# SenseBox-Shield_v10.net
KiCad netlist of a schematic drawn in EAGLE
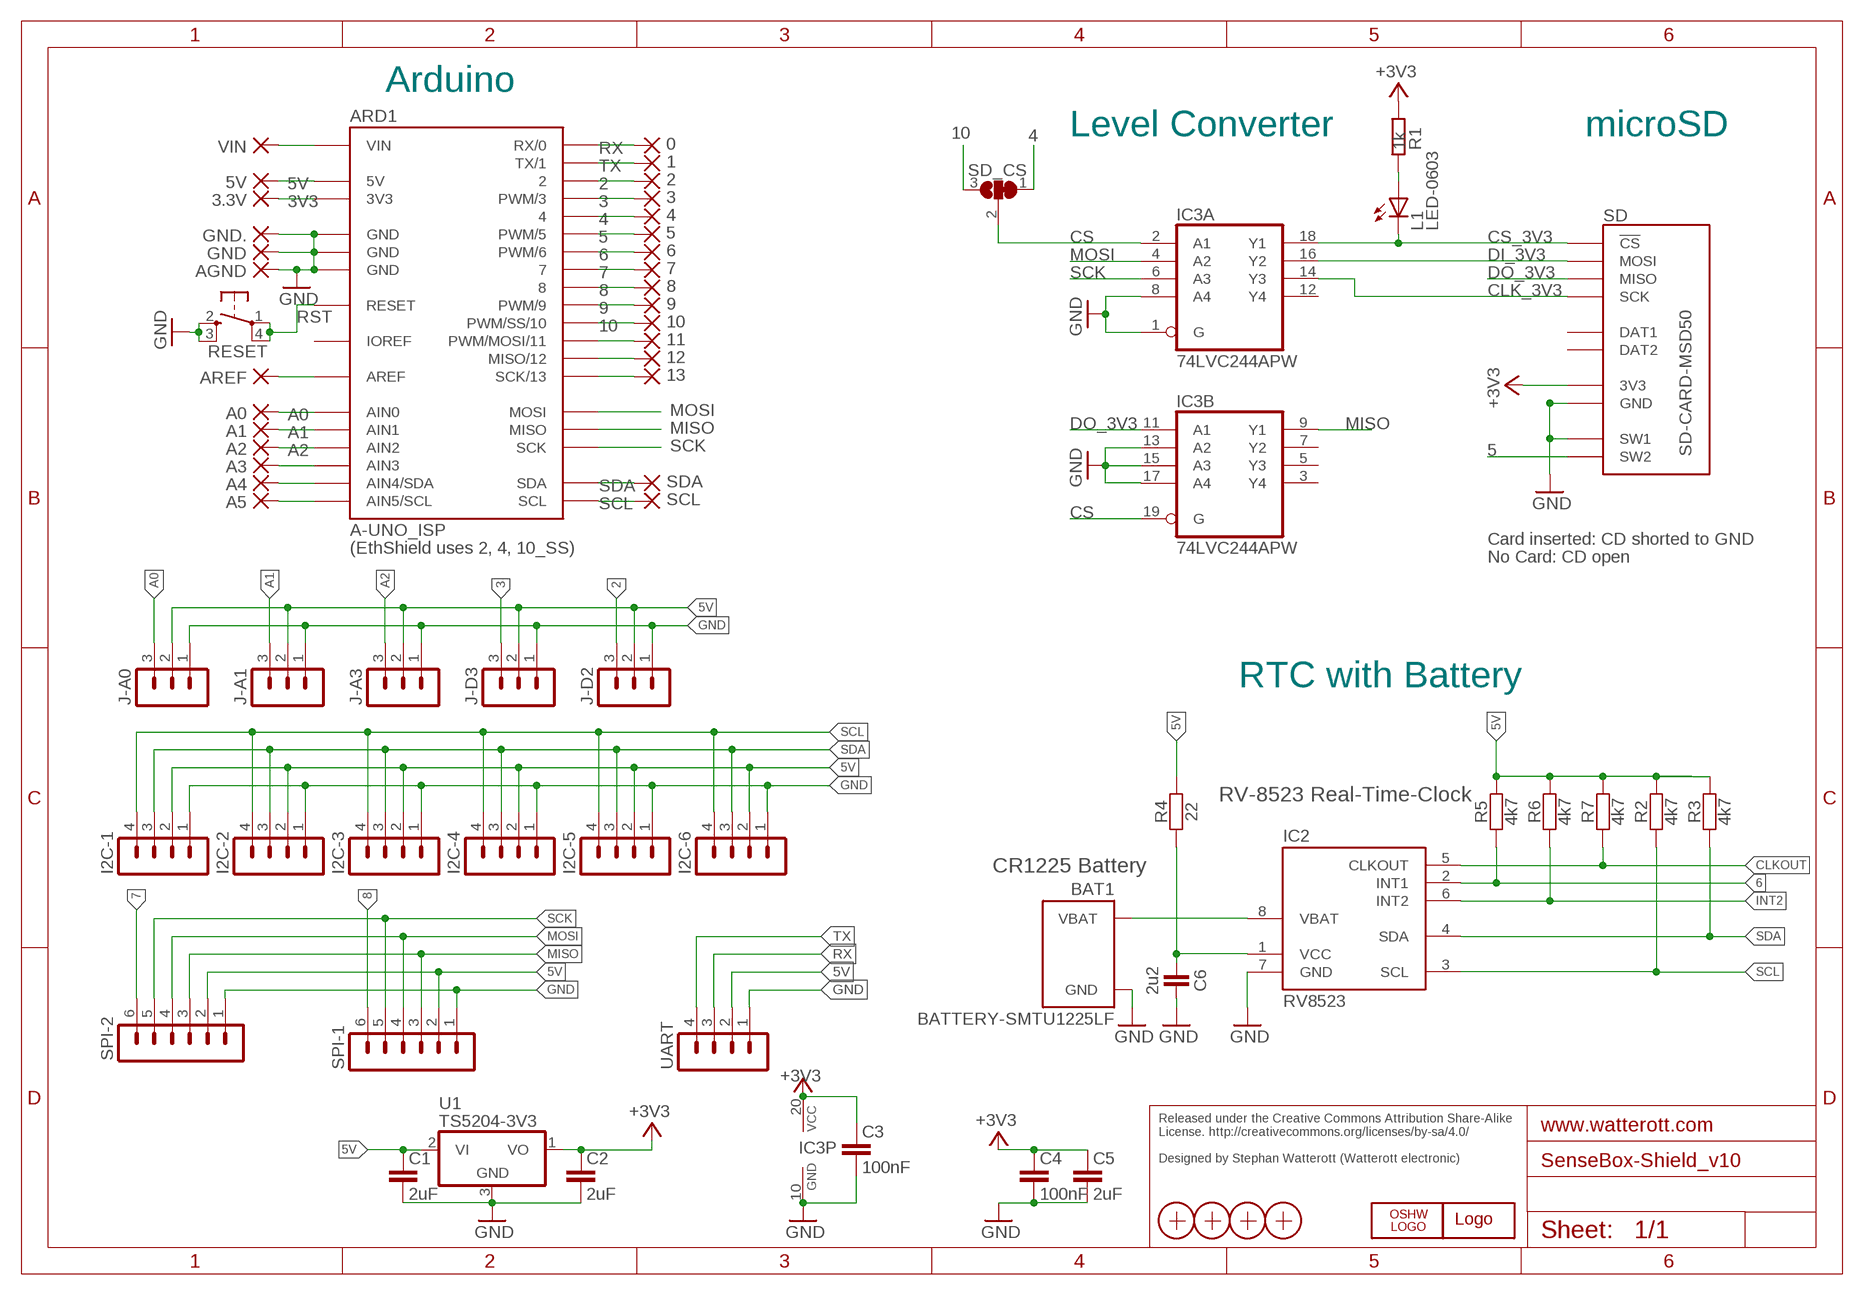
[diagram p0: schematic, sheet 1]

(export (version "E")
  (design (tool "Eeschema 10.0.6"))
  (components
    (comp (ref "0")
      (value "1,6/0,8")
      (footprint "eagle-import:1,6_0,8")
      (libsource (lib "eagle-import") (part "1,6/0,8"))
    )
    (comp (ref "1")
      (value "1,6/0,8")
      (footprint "eagle-import:1,6_0,8")
      (libsource (lib "eagle-import") (part "1,6/0,8"))
    )
    (comp (ref "2")
      (value "1,6/0,8")
      (footprint "eagle-import:1,6_0,8")
      (libsource (lib "eagle-import") (part "1,6/0,8"))
    )
    (comp (ref "3")
      (value "1,6/0,8")
      (footprint "eagle-import:1,6_0,8")
      (libsource (lib "eagle-import") (part "1,6/0,8"))
    )
    (comp (ref "3.3V")
      (value "1,6/0,8")
      (footprint "eagle-import:1,6_0,8")
      (libsource (lib "eagle-import") (part "1,6/0,8"))
    )
    (comp (ref "4")
      (value "1,6/0,8")
      (footprint "eagle-import:1,6_0,8")
      (libsource (lib "eagle-import") (part "1,6/0,8"))
    )
    (comp (ref "5")
      (value "1,6/0,8")
      (footprint "eagle-import:1,6_0,8")
      (libsource (lib "eagle-import") (part "1,6/0,8"))
    )
    (comp (ref "5V")
      (value "1,6/0,8")
      (footprint "eagle-import:1,6_0,8")
      (libsource (lib "eagle-import") (part "1,6/0,8"))
    )
    (comp (ref "6")
      (value "1,6/0,8")
      (footprint "eagle-import:1,6_0,8")
      (libsource (lib "eagle-import") (part "1,6/0,8"))
    )
    (comp (ref "7")
      (value "1,6/0,8")
      (footprint "eagle-import:1,6_0,8")
      (libsource (lib "eagle-import") (part "1,6/0,8"))
    )
    (comp (ref "8")
      (value "1,6/0,8")
      (footprint "eagle-import:1,6_0,8")
      (libsource (lib "eagle-import") (part "1,6/0,8"))
    )
    (comp (ref "9")
      (value "1,6/0,8")
      (footprint "eagle-import:1,6_0,8")
      (libsource (lib "eagle-import") (part "1,6/0,8"))
    )
    (comp (ref "10")
      (value "1,6/0,8")
      (footprint "eagle-import:1,6_0,8")
      (libsource (lib "eagle-import") (part "1,6/0,8"))
    )
    (comp (ref "11")
      (value "1,6/0,8")
      (footprint "eagle-import:1,6_0,8")
      (libsource (lib "eagle-import") (part "1,6/0,8"))
    )
    (comp (ref "12")
      (value "1,6/0,8")
      (footprint "eagle-import:1,6_0,8")
      (libsource (lib "eagle-import") (part "1,6/0,8"))
    )
    (comp (ref "13")
      (value "1,6/0,8")
      (footprint "eagle-import:1,6_0,8")
      (libsource (lib "eagle-import") (part "1,6/0,8"))
    )
    (comp (ref "A0")
      (value "1,6/0,8")
      (footprint "eagle-import:1,6_0,8")
      (libsource (lib "eagle-import") (part "1,6/0,8"))
    )
    (comp (ref "A1")
      (value "1,6/0,8")
      (footprint "eagle-import:1,6_0,8")
      (libsource (lib "eagle-import") (part "1,6/0,8"))
    )
    (comp (ref "A2")
      (value "1,6/0,8")
      (footprint "eagle-import:1,6_0,8")
      (libsource (lib "eagle-import") (part "1,6/0,8"))
    )
    (comp (ref "A3")
      (value "1,6/0,8")
      (footprint "eagle-import:1,6_0,8")
      (libsource (lib "eagle-import") (part "1,6/0,8"))
    )
    (comp (ref "A4")
      (value "1,6/0,8")
      (footprint "eagle-import:1,6_0,8")
      (libsource (lib "eagle-import") (part "1,6/0,8"))
    )
    (comp (ref "A5")
      (value "1,6/0,8")
      (footprint "eagle-import:1,6_0,8")
      (libsource (lib "eagle-import") (part "1,6/0,8"))
    )
    (comp (ref "AGND")
      (value "1,6/0,8")
      (footprint "eagle-import:1,6_0,8")
      (libsource (lib "eagle-import") (part "1,6/0,8"))
    )
    (comp (ref "ARD1")
      (value "A-UNO_ISP")
      (footprint "eagle-import:A-UNO-ISP")
      (libsource (lib "eagle-import") (part "A-UNO_ISP"))
    )
    (comp (ref "AREF")
      (value "1,6/0,8")
      (footprint "eagle-import:1,6_0,8")
      (libsource (lib "eagle-import") (part "1,6/0,8"))
    )
    (comp (ref "BAT1")
      (value "BATTERY-SMTU1225LF")
      (footprint "eagle-import:BAT-SMTU1225LF")
      (libsource (lib "eagle-import") (part "BATTERY-SMTU1225LF"))
    )
    (comp (ref "C1")
      (value "2uF")
      (footprint "eagle-import:C0805")
      (libsource (lib "eagle-import") (part "C-EUC0805"))
    )
    (comp (ref "C2")
      (value "2uF")
      (footprint "eagle-import:C0805")
      (libsource (lib "eagle-import") (part "C-EUC0805"))
    )
    (comp (ref "C3")
      (value "100nF")
      (footprint "eagle-import:C0603")
      (libsource (lib "eagle-import") (part "C-EUC0603"))
    )
    (comp (ref "C4")
      (value "100nF")
      (footprint "eagle-import:C0603")
      (libsource (lib "eagle-import") (part "C-EUC0603"))
    )
    (comp (ref "C5")
      (value "2uF")
      (footprint "eagle-import:C0603")
      (libsource (lib "eagle-import") (part "C-EUC0603"))
    )
    (comp (ref "C6")
      (value "2u2")
      (footprint "eagle-import:R0603")
      (libsource (lib "eagle-import") (part "CAPACITOR-C0603"))
    )
    (comp (ref "GND")
      (value "1,6/0,8")
      (footprint "eagle-import:1,6_0,8")
      (libsource (lib "eagle-import") (part "1,6/0,8"))
    )
    (comp (ref "GND.")
      (value "1,6/0,8")
      (footprint "eagle-import:1,6_0,8")
      (libsource (lib "eagle-import") (part "1,6/0,8"))
    )
    (comp (ref "I2C-1")
      (value "JST_PH_4B4B-PH-SM4-TB")
      (footprint "eagle-import:JST_B4B-PH-SM4-TB")
      (libsource (lib "eagle-import") (part "JST_PH_4B4B-PH-SM4-TB"))
    )
    (comp (ref "I2C-2")
      (value "JST_PH_4B4B-PH-SM4-TB")
      (footprint "eagle-import:JST_B4B-PH-SM4-TB")
      (libsource (lib "eagle-import") (part "JST_PH_4B4B-PH-SM4-TB"))
    )
    (comp (ref "I2C-3")
      (value "JST_PH_4B4B-PH-SM4-TB")
      (footprint "eagle-import:JST_B4B-PH-SM4-TB")
      (libsource (lib "eagle-import") (part "JST_PH_4B4B-PH-SM4-TB"))
    )
    (comp (ref "I2C-4")
      (value "JST_PH_4B4B-PH-SM4-TB")
      (footprint "eagle-import:JST_B4B-PH-SM4-TB")
      (libsource (lib "eagle-import") (part "JST_PH_4B4B-PH-SM4-TB"))
    )
    (comp (ref "I2C-5")
      (value "JST_PH_4B4B-PH-SM4-TB")
      (footprint "eagle-import:JST_B4B-PH-SM4-TB")
      (libsource (lib "eagle-import") (part "JST_PH_4B4B-PH-SM4-TB"))
    )
    (comp (ref "I2C-6")
      (value "JST_PH_4B4B-PH-SM4-TB")
      (footprint "eagle-import:JST_B4B-PH-SM4-TB")
      (libsource (lib "eagle-import") (part "JST_PH_4B4B-PH-SM4-TB"))
    )
    (comp (ref "IC2")
      (value "RV8523")
      (footprint "eagle-import:RTC-C3")
      (libsource (lib "eagle-import") (part "RV8523-C3"))
    )
    (comp (ref "IC3")
      (value "74LVC244APW")
      (footprint "eagle-import:TSSOP20")
      (libsource (lib "eagle-import") (part "74244PWLVC"))
    )
    (comp (ref "J-A0")
      (value "JST_PH_3B3B-PH-SM4-TB")
      (footprint "eagle-import:JST_B3B-PH-SM4-TB")
      (libsource (lib "eagle-import") (part "JST_PH_3B3B-PH-SM4-TB"))
    )
    (comp (ref "J-A1")
      (value "JST_PH_3B3B-PH-SM4-TB")
      (footprint "eagle-import:JST_B3B-PH-SM4-TB")
      (libsource (lib "eagle-import") (part "JST_PH_3B3B-PH-SM4-TB"))
    )
    (comp (ref "J-A3")
      (value "JST_PH_3B3B-PH-SM4-TB")
      (footprint "eagle-import:JST_B3B-PH-SM4-TB")
      (libsource (lib "eagle-import") (part "JST_PH_3B3B-PH-SM4-TB"))
    )
    (comp (ref "J-D2")
      (value "JST_PH_3B3B-PH-SM4-TB")
      (footprint "eagle-import:JST_B3B-PH-SM4-TB")
      (libsource (lib "eagle-import") (part "JST_PH_3B3B-PH-SM4-TB"))
    )
    (comp (ref "J-D3")
      (value "JST_PH_3B3B-PH-SM4-TB")
      (footprint "eagle-import:JST_B3B-PH-SM4-TB")
      (libsource (lib "eagle-import") (part "JST_PH_3B3B-PH-SM4-TB"))
    )
    (comp (ref "L1")
      (value "LED-0603")
      (footprint "eagle-import:LED_0603")
      (libsource (lib "eagle-import") (part "LED-0603"))
    )
    (comp (ref "LOGO2")
      (value "WE-LOGOPLACE")
      (footprint "eagle-import:WE-LOGO")
      (libsource (lib "eagle-import") (part "WE-LOGOPLACE"))
    )
    (comp (ref "LOGO3")
      (value "OSHW_LOGO_6MILX0100-NT")
      (footprint "eagle-import:OSHW_6X100_NOTEXT")
      (libsource (lib "eagle-import") (part "OSHW_LOGO_6MILX0100-NT"))
    )
    (comp (ref "R1")
      (value "1k")
      (footprint "eagle-import:R0603")
      (libsource (lib "eagle-import") (part "R-EU_R0603"))
    )
    (comp (ref "R2")
      (value "4k7")
      (footprint "eagle-import:R0603")
      (libsource (lib "eagle-import") (part "RESISTOR-R0603"))
    )
    (comp (ref "R3")
      (value "4k7")
      (footprint "eagle-import:R0603")
      (libsource (lib "eagle-import") (part "RESISTOR-R0603"))
    )
    (comp (ref "R4")
      (value "22")
      (footprint "eagle-import:R0603")
      (libsource (lib "eagle-import") (part "RESISTOR-R0603"))
    )
    (comp (ref "R5")
      (value "4k7")
      (footprint "eagle-import:R0603")
      (libsource (lib "eagle-import") (part "RESISTOR-R0603"))
    )
    (comp (ref "R6")
      (value "4k7")
      (footprint "eagle-import:R0603")
      (libsource (lib "eagle-import") (part "RESISTOR-R0603"))
    )
    (comp (ref "R7")
      (value "4k7")
      (footprint "eagle-import:R0603")
      (libsource (lib "eagle-import") (part "RESISTOR-R0603"))
    )
    (comp (ref "RESET")
      (value "SW4S")
      (footprint "eagle-import:SW_SMD4")
      (libsource (lib "eagle-import") (part "SW4S"))
    )
    (comp (ref "SCL")
      (value "1,6/0,8")
      (footprint "eagle-import:1,6_0,8")
      (libsource (lib "eagle-import") (part "1,6/0,8"))
    )
    (comp (ref "SD")
      (value "SD-CARD-MSD50")
      (footprint "eagle-import:SD_5031821853")
      (libsource (lib "eagle-import") (part "SD-CARD-MSD50"))
    )
    (comp (ref "SDA")
      (value "1,6/0,8")
      (footprint "eagle-import:1,6_0,8")
      (libsource (lib "eagle-import") (part "1,6/0,8"))
    )
    (comp (ref "SD_CS")
      (value "SJ2W")
      (footprint "eagle-import:SJ_2")
      (libsource (lib "eagle-import") (part "SJ2W"))
    )
    (comp (ref "SPI-1")
      (value "JST_PH_6B6B-PH-SM4-TB")
      (footprint "eagle-import:JST_B6B-PH-SM4-TB")
      (libsource (lib "eagle-import") (part "JST_PH_6B6B-PH-SM4-TB"))
    )
    (comp (ref "SPI-2")
      (value "JST_PH_6B6B-PH-SM4-TB")
      (footprint "eagle-import:JST_B6B-PH-SM4-TB")
      (libsource (lib "eagle-import") (part "JST_PH_6B6B-PH-SM4-TB"))
    )
    (comp (ref "U1")
      (value "TS5204-3V3")
      (footprint "eagle-import:SOT23")
      (libsource (lib "eagle-import") (part "TS5204"))
    )
    (comp (ref "UART")
      (value "JST_PH_4B4B-PH-SM4-TB")
      (footprint "eagle-import:JST_B4B-PH-SM4-TB")
      (libsource (lib "eagle-import") (part "JST_PH_4B4B-PH-SM4-TB"))
    )
    (comp (ref "VIN")
      (value "1,6/0,8")
      (footprint "eagle-import:1,6_0,8")
      (libsource (lib "eagle-import") (part "1,6/0,8"))
    )
    (comp (ref "X1")
      (value "PASSER")
      (footprint "eagle-import:PASSER")
      (libsource (lib "eagle-import") (part "PASSER"))
    )
    (comp (ref "X2")
      (value "PASSER")
      (footprint "eagle-import:PASSER")
      (libsource (lib "eagle-import") (part "PASSER"))
    )
    (comp (ref "X3")
      (value "PASSER")
      (footprint "eagle-import:PASSER")
      (libsource (lib "eagle-import") (part "PASSER"))
    )
    (comp (ref "X4")
      (value "PASSER")
      (footprint "eagle-import:PASSER")
      (libsource (lib "eagle-import") (part "PASSER"))
    )
  )
  (nets
    (net (code "1") (name "+3V3") (class "Default")
      (node (ref "C2") (pin "1") (pinfunction "1_1") (pintype "passive"))
      (node (ref "C3") (pin "1") (pinfunction "1_1") (pintype "passive"))
      (node (ref "C4") (pin "1") (pinfunction "1_1") (pintype "passive"))
      (node (ref "C5") (pin "1") (pinfunction "1_1") (pintype "passive"))
      (node (ref "IC3") (pin "20") (pinfunction "VCC_20") (pintype "power_in"))
      (node (ref "R1") (pin "1") (pinfunction "1_1") (pintype "passive"))
      (node (ref "SD") (pin "VCC") (pinfunction "3V3_VCC") (pintype "bidirectional"))
      (node (ref "U1") (pin "1") (pinfunction "VO_1") (pintype "passive"))
    )
    (net (code "2") (name "/3V3") (class "Default")
      (node (ref "3.3V") (pin "1") (pinfunction "P_1") (pintype "passive"))
      (node (ref "ARD1") (pin "3V3") (pinfunction "3V3_3V3") (pintype "power_in"))
    )
    (net (code "3") (name "/4") (class "Default")
      (node (ref "4") (pin "1") (pinfunction "P_1") (pintype "passive"))
      (node (ref "ARD1") (pin "4") (pinfunction "4_4") (pintype "bidirectional"))
      (node (ref "SD_CS") (pin "1") (pinfunction "1_1") (pintype "passive"))
    )
    (net (code "4") (name "/5") (class "Default")
      (node (ref "5") (pin "1") (pinfunction "P_1") (pintype "passive"))
      (node (ref "ARD1") (pin "5") (pinfunction "PWM/5_5") (pintype "bidirectional"))
      (node (ref "SD") (pin "SW2") (pinfunction "SW2_SW2") (pintype "bidirectional"))
    )
    (net (code "5") (name "/9") (class "Default")
      (node (ref "9") (pin "1") (pinfunction "P_1") (pintype "passive"))
      (node (ref "ARD1") (pin "9") (pinfunction "PWM/9_9") (pintype "bidirectional"))
    )
    (net (code "6") (name "/10") (class "Default")
      (node (ref "10") (pin "1") (pinfunction "P_1") (pintype "passive"))
      (node (ref "ARD1") (pin "10") (pinfunction "PWM/SS/10_10") (pintype "bidirectional"))
      (node (ref "SD_CS") (pin "3") (pinfunction "3_3") (pintype "passive"))
    )
    (net (code "7") (name "/CLK_3V3") (class "Default")
      (node (ref "IC3") (pin "14") (pinfunction "Y3_14") (pintype "tri_state"))
      (node (ref "SD") (pin "SCK") (pinfunction "SCK_SCK") (pintype "bidirectional"))
    )
    (net (code "8") (name "/CS") (class "Default")
      (node (ref "IC3") (pin "19") (pinfunction "G_19") (pintype "input"))
      (node (ref "IC3") (pin "2") (pinfunction "A1_2") (pintype "input"))
      (node (ref "SD_CS") (pin "2") (pinfunction "2_2") (pintype "passive"))
    )
    (net (code "9") (name "/CS_3V3") (class "Default")
      (node (ref "IC3") (pin "18") (pinfunction "Y1_18") (pintype "tri_state"))
      (node (ref "L1") (pin "C") (pinfunction "C_C") (pintype "passive"))
      (node (ref "SD") (pin "CS") (pinfunction "~{CS}_CS") (pintype "bidirectional"))
    )
    (net (code "10") (name "/DI_3V3") (class "Default")
      (node (ref "IC3") (pin "16") (pinfunction "Y2_16") (pintype "tri_state"))
      (node (ref "SD") (pin "MOSI") (pinfunction "MOSI_MOSI") (pintype "bidirectional"))
    )
    (net (code "11") (name "/DO_3V3") (class "Default")
      (node (ref "IC3") (pin "11") (pinfunction "A1_11") (pintype "input"))
      (node (ref "SD") (pin "MISO") (pinfunction "MISO_MISO") (pintype "bidirectional"))
    )
    (net (code "12") (name "/IOREF") (class "Default")
      (node (ref "ARD1") (pin "IOREF") (pinfunction "IOREF_IOREF") (pintype "power_in"))
    )
    (net (code "13") (name "/RST") (class "Default")
      (node (ref "ARD1") (pin "RST") (pinfunction "RESET_RST") (pintype "bidirectional"))
      (node (ref "RESET") (pin "1") (pinfunction "P_1") (pintype "passive"))
      (node (ref "RESET") (pin "4") (pinfunction "P1_4") (pintype "passive"))
    )
    (net (code "14") (name "2") (class "Default")
      (node (ref "2") (pin "1") (pinfunction "P_1") (pintype "passive"))
      (node (ref "ARD1") (pin "2") (pinfunction "2_2") (pintype "bidirectional"))
      (node (ref "J-D2") (pin "3") (pinfunction "3_3") (pintype "passive"))
    )
    (net (code "15") (name "3") (class "Default")
      (node (ref "3") (pin "1") (pinfunction "P_1") (pintype "passive"))
      (node (ref "ARD1") (pin "3") (pinfunction "PWM/3_3") (pintype "bidirectional"))
      (node (ref "J-D3") (pin "3") (pinfunction "3_3") (pintype "passive"))
    )
    (net (code "16") (name "5V") (class "Default")
      (node (ref "5V") (pin "1") (pinfunction "P_1") (pintype "passive"))
      (node (ref "ARD1") (pin "5V") (pinfunction "5V_5V") (pintype "power_in"))
      (node (ref "C1") (pin "1") (pinfunction "1_1") (pintype "passive"))
      (node (ref "I2C-1") (pin "2") (pinfunction "2_2") (pintype "passive"))
      (node (ref "I2C-2") (pin "2") (pinfunction "2_2") (pintype "passive"))
      (node (ref "I2C-3") (pin "2") (pinfunction "2_2") (pintype "passive"))
      (node (ref "I2C-4") (pin "2") (pinfunction "2_2") (pintype "passive"))
      (node (ref "I2C-5") (pin "2") (pinfunction "2_2") (pintype "passive"))
      (node (ref "I2C-6") (pin "2") (pinfunction "2_2") (pintype "passive"))
      (node (ref "J-A0") (pin "2") (pinfunction "2_2") (pintype "passive"))
      (node (ref "J-A1") (pin "2") (pinfunction "2_2") (pintype "passive"))
      (node (ref "J-A3") (pin "2") (pinfunction "2_2") (pintype "passive"))
      (node (ref "J-D2") (pin "2") (pinfunction "2_2") (pintype "passive"))
      (node (ref "J-D3") (pin "2") (pinfunction "2_2") (pintype "passive"))
      (node (ref "R2") (pin "2") (pinfunction "2_2") (pintype "passive"))
      (node (ref "R3") (pin "2") (pinfunction "2_2") (pintype "passive"))
      (node (ref "R4") (pin "2") (pinfunction "2_2") (pintype "passive"))
      (node (ref "R5") (pin "2") (pinfunction "2_2") (pintype "passive"))
      (node (ref "R6") (pin "2") (pinfunction "2_2") (pintype "passive"))
      (node (ref "R7") (pin "2") (pinfunction "2_2") (pintype "passive"))
      (node (ref "SPI-1") (pin "2") (pinfunction "2_2") (pintype "passive"))
      (node (ref "SPI-2") (pin "2") (pinfunction "2_2") (pintype "passive"))
      (node (ref "U1") (pin "2") (pinfunction "VI_2") (pintype "input"))
      (node (ref "UART") (pin "2") (pinfunction "2_2") (pintype "passive"))
    )
    (net (code "17") (name "6") (class "Default")
      (node (ref "6") (pin "1") (pinfunction "P_1") (pintype "passive"))
      (node (ref "ARD1") (pin "6") (pinfunction "PWM/6_6") (pintype "bidirectional"))
      (node (ref "IC2") (pin "2") (pinfunction "INT1_2") (pintype "bidirectional"))
      (node (ref "R5") (pin "1") (pinfunction "1_1") (pintype "passive"))
    )
    (net (code "18") (name "7") (class "Default")
      (node (ref "7") (pin "1") (pinfunction "P_1") (pintype "passive"))
      (node (ref "ARD1") (pin "7") (pinfunction "7_7") (pintype "bidirectional"))
      (node (ref "SPI-2") (pin "6") (pinfunction "6_6") (pintype "passive"))
    )
    (net (code "19") (name "8") (class "Default")
      (node (ref "8") (pin "1") (pinfunction "P_1") (pintype "passive"))
      (node (ref "ARD1") (pin "8") (pinfunction "8_8") (pintype "bidirectional"))
      (node (ref "SPI-1") (pin "6") (pinfunction "6_6") (pintype "passive"))
    )
    (net (code "20") (name "A0") (class "Default")
      (node (ref "A0") (pin "1") (pinfunction "P_1") (pintype "passive"))
      (node (ref "ARD1") (pin "A0") (pinfunction "AIN0_A0") (pintype "bidirectional"))
      (node (ref "J-A0") (pin "3") (pinfunction "3_3") (pintype "passive"))
    )
    (net (code "21") (name "A1") (class "Default")
      (node (ref "A1") (pin "1") (pinfunction "P_1") (pintype "passive"))
      (node (ref "ARD1") (pin "A1") (pinfunction "AIN1_A1") (pintype "bidirectional"))
      (node (ref "J-A1") (pin "3") (pinfunction "3_3") (pintype "passive"))
    )
    (net (code "22") (name "A2") (class "Default")
      (node (ref "A2") (pin "1") (pinfunction "P_1") (pintype "passive"))
      (node (ref "ARD1") (pin "A2") (pinfunction "AIN2_A2") (pintype "bidirectional"))
      (node (ref "J-A3") (pin "3") (pinfunction "3_3") (pintype "passive"))
    )
    (net (code "23") (name "CLKOUT") (class "Default")
      (node (ref "IC2") (pin "5") (pinfunction "CLKOUT_5") (pintype "bidirectional"))
      (node (ref "R7") (pin "1") (pinfunction "1_1") (pintype "passive"))
    )
    (net (code "24") (name "GND") (class "Default")
      (node (ref "AGND") (pin "1") (pinfunction "P_1") (pintype "passive"))
      (node (ref "ARD1") (pin "GND@1") (pinfunction "GND_GND@1") (pintype "power_in"))
      (node (ref "ARD1") (pin "GND@2") (pinfunction "GND_GND@2") (pintype "power_in"))
      (node (ref "ARD1") (pin "GND@3") (pinfunction "GND_GND@3") (pintype "power_in"))
      (node (ref "BAT1") (pin "-") (pinfunction "GND_-") (pintype "passive"))
      (node (ref "C1") (pin "2") (pinfunction "2_2") (pintype "passive"))
      (node (ref "C2") (pin "2") (pinfunction "2_2") (pintype "passive"))
      (node (ref "C3") (pin "2") (pinfunction "2_2") (pintype "passive"))
      (node (ref "C4") (pin "2") (pinfunction "2_2") (pintype "passive"))
      (node (ref "C5") (pin "2") (pinfunction "2_2") (pintype "passive"))
      (node (ref "C6") (pin "2") (pinfunction "2_2") (pintype "passive"))
      (node (ref "GND") (pin "1") (pinfunction "P_1") (pintype "passive"))
      (node (ref "GND.") (pin "1") (pinfunction "P_1") (pintype "passive"))
      (node (ref "I2C-1") (pin "1") (pinfunction "1_1") (pintype "passive"))
      (node (ref "I2C-2") (pin "1") (pinfunction "1_1") (pintype "passive"))
      (node (ref "I2C-3") (pin "1") (pinfunction "1_1") (pintype "passive"))
      (node (ref "I2C-4") (pin "1") (pinfunction "1_1") (pintype "passive"))
      (node (ref "I2C-5") (pin "1") (pinfunction "1_1") (pintype "passive"))
      (node (ref "I2C-6") (pin "1") (pinfunction "1_1") (pintype "passive"))
      (node (ref "IC2") (pin "7") (pinfunction "GND_7") (pintype "power_in"))
      (node (ref "IC3") (pin "1") (pinfunction "G_1") (pintype "input"))
      (node (ref "IC3") (pin "10") (pinfunction "GND_10") (pintype "power_in"))
      (node (ref "IC3") (pin "13") (pinfunction "A2_13") (pintype "input"))
      (node (ref "IC3") (pin "15") (pinfunction "A3_15") (pintype "input"))
      (node (ref "IC3") (pin "17") (pinfunction "A4_17") (pintype "input"))
      (node (ref "IC3") (pin "8") (pinfunction "A4_8") (pintype "input"))
      (node (ref "J-A0") (pin "1") (pinfunction "1_1") (pintype "passive"))
      (node (ref "J-A1") (pin "1") (pinfunction "1_1") (pintype "passive"))
      (node (ref "J-A3") (pin "1") (pinfunction "1_1") (pintype "passive"))
      (node (ref "J-D2") (pin "1") (pinfunction "1_1") (pintype "passive"))
      (node (ref "J-D3") (pin "1") (pinfunction "1_1") (pintype "passive"))
      (node (ref "RESET") (pin "2") (pinfunction "S_2") (pintype "passive"))
      (node (ref "RESET") (pin "3") (pinfunction "S1_3") (pintype "passive"))
      (node (ref "SD") (pin "GND") (pinfunction "GND_GND") (pintype "bidirectional"))
      (node (ref "SD") (pin "SW1") (pinfunction "SW1_SW1") (pintype "bidirectional"))
      (node (ref "SPI-1") (pin "1") (pinfunction "1_1") (pintype "passive"))
      (node (ref "SPI-2") (pin "1") (pinfunction "1_1") (pintype "passive"))
      (node (ref "U1") (pin "3") (pinfunction "GND_3") (pintype "passive"))
      (node (ref "UART") (pin "1") (pinfunction "1_1") (pintype "passive"))
    )
    (net (code "25") (name "INT2") (class "Default")
      (node (ref "IC2") (pin "6") (pinfunction "INT2_6") (pintype "bidirectional"))
      (node (ref "R6") (pin "1") (pinfunction "1_1") (pintype "passive"))
    )
    (net (code "26") (name "MISO") (class "Default")
      (node (ref "ARD1") (pin "MISO") (pinfunction "MISO_MISO") (pintype "bidirectional"))
      (node (ref "IC3") (pin "9") (pinfunction "Y1_9") (pintype "tri_state"))
      (node (ref "SPI-1") (pin "3") (pinfunction "3_3") (pintype "passive"))
      (node (ref "SPI-2") (pin "3") (pinfunction "3_3") (pintype "passive"))
    )
    (net (code "27") (name "MOSI") (class "Default")
      (node (ref "ARD1") (pin "MOSI") (pinfunction "MOSI_MOSI") (pintype "bidirectional"))
      (node (ref "IC3") (pin "4") (pinfunction "A2_4") (pintype "input"))
      (node (ref "SPI-1") (pin "4") (pinfunction "4_4") (pintype "passive"))
      (node (ref "SPI-2") (pin "4") (pinfunction "4_4") (pintype "passive"))
    )
    (net (code "28") (name "Net-(11-P)") (class "Default")
      (node (ref "11") (pin "1") (pinfunction "P_1") (pintype "passive"))
      (node (ref "ARD1") (pin "11") (pinfunction "PWM/MOSI/11_11") (pintype "bidirectional"))
    )
    (net (code "29") (name "Net-(12-P)") (class "Default")
      (node (ref "12") (pin "1") (pinfunction "P_1") (pintype "passive"))
      (node (ref "ARD1") (pin "12") (pinfunction "MISO/12_12") (pintype "bidirectional"))
    )
    (net (code "30") (name "Net-(13-P)") (class "Default")
      (node (ref "13") (pin "1") (pinfunction "P_1") (pintype "passive"))
      (node (ref "ARD1") (pin "13") (pinfunction "SCK/13_13") (pintype "bidirectional"))
    )
    (net (code "31") (name "Net-(A3-P)") (class "Default")
      (node (ref "A3") (pin "1") (pinfunction "P_1") (pintype "passive"))
      (node (ref "ARD1") (pin "A3") (pinfunction "AIN3_A3") (pintype "bidirectional"))
    )
    (net (code "32") (name "Net-(A4-P)") (class "Default")
      (node (ref "A4") (pin "1") (pinfunction "P_1") (pintype "passive"))
      (node (ref "ARD1") (pin "A4") (pinfunction "AIN4/SDA_A4") (pintype "bidirectional"))
    )
    (net (code "33") (name "Net-(A5-P)") (class "Default")
      (node (ref "A5") (pin "1") (pinfunction "P_1") (pintype "passive"))
      (node (ref "ARD1") (pin "A5") (pinfunction "AIN5/SCL_A5") (pintype "bidirectional"))
    )
    (net (code "34") (name "Net-(AREF-P)") (class "Default")
      (node (ref "ARD1") (pin "AREF") (pinfunction "AREF_AREF") (pintype "power_in"))
      (node (ref "AREF") (pin "1") (pinfunction "P_1") (pintype "passive"))
    )
    (net (code "35") (name "Net-(BAT1-VBAT)") (class "Default")
      (node (ref "BAT1") (pin "+") (pinfunction "VBAT_+") (pintype "passive"))
      (node (ref "IC2") (pin "8") (pinfunction "VBAT_8") (pintype "power_in"))
    )
    (net (code "36") (name "Net-(IC2-VCC)") (class "Default")
      (node (ref "C6") (pin "1") (pinfunction "1_1") (pintype "passive"))
      (node (ref "IC2") (pin "1") (pinfunction "VCC_1") (pintype "power_in"))
      (node (ref "R4") (pin "1") (pinfunction "1_1") (pintype "passive"))
    )
    (net (code "37") (name "Net-(L1-PadA)") (class "Default")
      (node (ref "L1") (pin "A") (pinfunction "A_A") (pintype "passive"))
      (node (ref "R1") (pin "2") (pinfunction "2_2") (pintype "passive"))
    )
    (net (code "38") (name "Net-(VIN-P)") (class "Default")
      (node (ref "ARD1") (pin "VIN") (pinfunction "VIN_VIN") (pintype "power_in"))
      (node (ref "VIN") (pin "1") (pinfunction "P_1") (pintype "passive"))
    )
    (net (code "39") (name "RX") (class "Default")
      (node (ref "0") (pin "1") (pinfunction "P_1") (pintype "passive"))
      (node (ref "ARD1") (pin "0") (pinfunction "RX/0_0") (pintype "bidirectional"))
      (node (ref "UART") (pin "3") (pinfunction "3_3") (pintype "passive"))
    )
    (net (code "40") (name "SCK") (class "Default")
      (node (ref "ARD1") (pin "SCK") (pinfunction "SCK_SCK") (pintype "bidirectional"))
      (node (ref "IC3") (pin "6") (pinfunction "A3_6") (pintype "input"))
      (node (ref "SPI-1") (pin "5") (pinfunction "5_5") (pintype "passive"))
      (node (ref "SPI-2") (pin "5") (pinfunction "5_5") (pintype "passive"))
    )
    (net (code "41") (name "SCL") (class "Default")
      (node (ref "ARD1") (pin "SCL") (pinfunction "SCL_SCL") (pintype "bidirectional"))
      (node (ref "I2C-1") (pin "4") (pinfunction "4_4") (pintype "passive"))
      (node (ref "I2C-2") (pin "4") (pinfunction "4_4") (pintype "passive"))
      (node (ref "I2C-3") (pin "4") (pinfunction "4_4") (pintype "passive"))
      (node (ref "I2C-4") (pin "4") (pinfunction "4_4") (pintype "passive"))
      (node (ref "I2C-5") (pin "4") (pinfunction "4_4") (pintype "passive"))
      (node (ref "I2C-6") (pin "4") (pinfunction "4_4") (pintype "passive"))
      (node (ref "IC2") (pin "3") (pinfunction "SCL_3") (pintype "bidirectional"))
      (node (ref "R2") (pin "1") (pinfunction "1_1") (pintype "passive"))
      (node (ref "SCL") (pin "1") (pinfunction "P_1") (pintype "passive"))
    )
    (net (code "42") (name "SDA") (class "Default")
      (node (ref "ARD1") (pin "SDA") (pinfunction "SDA_SDA") (pintype "bidirectional"))
      (node (ref "I2C-1") (pin "3") (pinfunction "3_3") (pintype "passive"))
      (node (ref "I2C-2") (pin "3") (pinfunction "3_3") (pintype "passive"))
      (node (ref "I2C-3") (pin "3") (pinfunction "3_3") (pintype "passive"))
      (node (ref "I2C-4") (pin "3") (pinfunction "3_3") (pintype "passive"))
      (node (ref "I2C-5") (pin "3") (pinfunction "3_3") (pintype "passive"))
      (node (ref "I2C-6") (pin "3") (pinfunction "3_3") (pintype "passive"))
      (node (ref "IC2") (pin "4") (pinfunction "SDA_4") (pintype "bidirectional"))
      (node (ref "R3") (pin "1") (pinfunction "1_1") (pintype "passive"))
      (node (ref "SDA") (pin "1") (pinfunction "P_1") (pintype "passive"))
    )
    (net (code "43") (name "TX") (class "Default")
      (node (ref "1") (pin "1") (pinfunction "P_1") (pintype "passive"))
      (node (ref "ARD1") (pin "1") (pinfunction "TX/1_1") (pintype "bidirectional"))
      (node (ref "UART") (pin "4") (pinfunction "4_4") (pintype "passive"))
    )
    (net (code "44") (name "unconnected-(IC3A-Y4-Pad12)") (class "Default")
      (node (ref "IC3") (pin "12") (pinfunction "Y4_12") (pintype "tri_state"))
    )
    (net (code "45") (name "unconnected-(IC3B-Y2-Pad7)") (class "Default")
      (node (ref "IC3") (pin "7") (pinfunction "Y2_7") (pintype "tri_state"))
    )
    (net (code "46") (name "unconnected-(IC3B-Y3-Pad5)") (class "Default")
      (node (ref "IC3") (pin "5") (pinfunction "Y3_5") (pintype "tri_state"))
    )
    (net (code "47") (name "unconnected-(IC3B-Y4-Pad3)") (class "Default")
      (node (ref "IC3") (pin "3") (pinfunction "Y4_3") (pintype "tri_state"))
    )
    (net (code "48") (name "unconnected-(SD-PadDAT1)") (class "Default")
      (node (ref "SD") (pin "DAT1") (pinfunction "DAT1_DAT1") (pintype "bidirectional"))
    )
    (net (code "49") (name "unconnected-(SD-PadDAT2)") (class "Default")
      (node (ref "SD") (pin "DAT2") (pinfunction "DAT2_DAT2") (pintype "bidirectional"))
    )
  )
)
